# LoRaLo_V30a.net
KiCad netlist of a schematic drawn in EAGLE
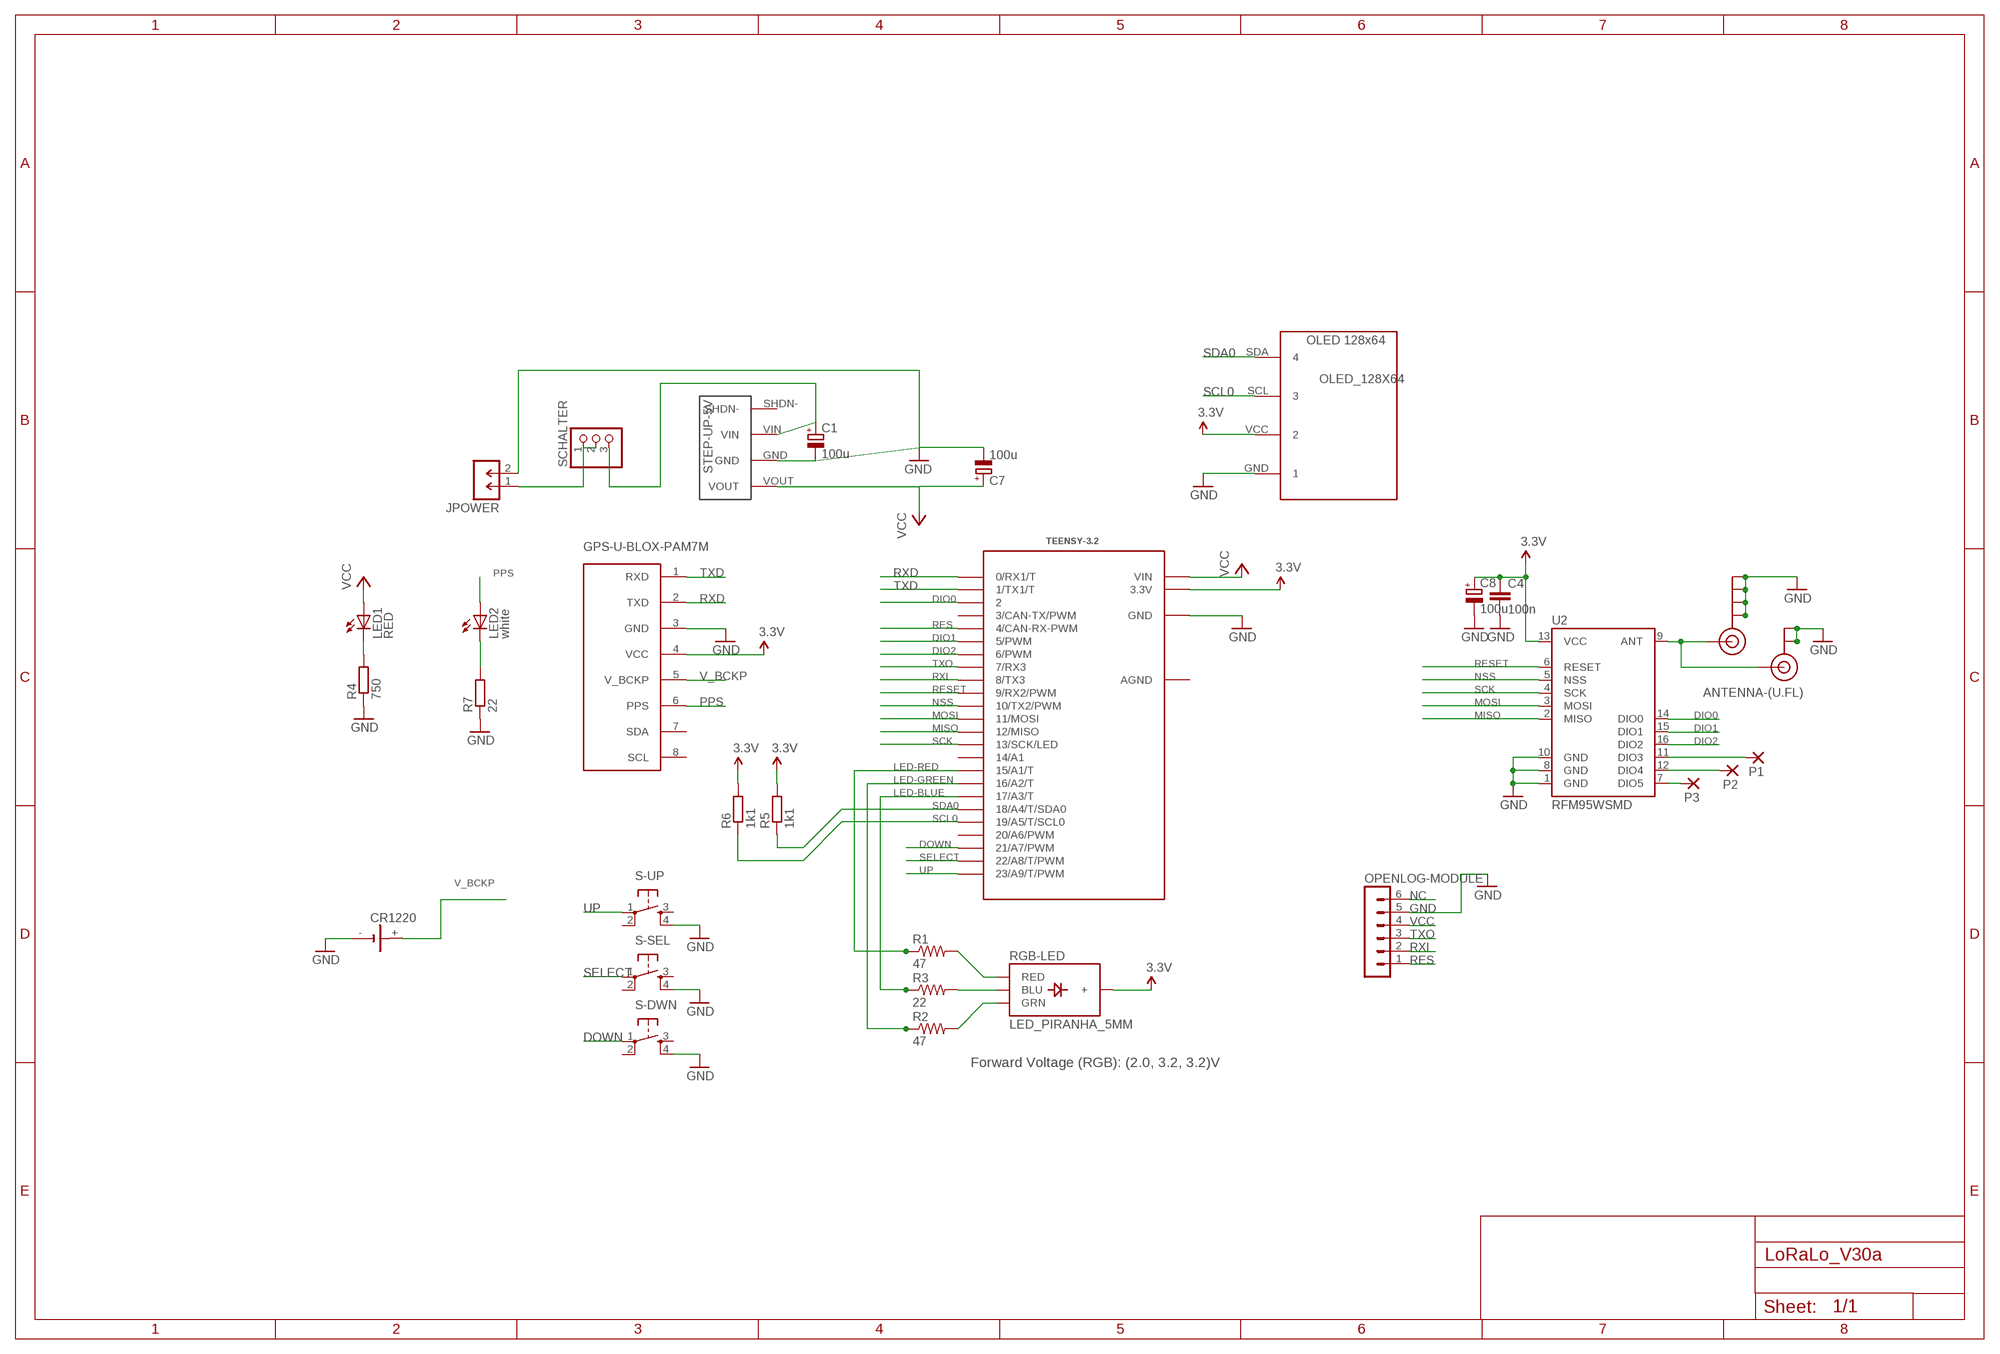
[diagram p0: schematic, sheet 1]

(export (version "E")
  (design (tool "Eeschema 10.0.6"))
  (components
    (comp (ref "ANTENNA-(EDGE-MOUNT)")
      (value "SMA_EDGE")
      (footprint "eagle-import:SMA-EDGE")
      (libsource (lib "eagle-import") (part "SMA_EDGE"))
    )
    (comp (ref "ANTENNA-(U.FL)")
      (value "U.FL")
      (footprint "eagle-import:U.FL")
      (libsource (lib "eagle-import") (part "U.FL"))
    )
    (comp (ref "C1")
      (value "100u")
      (footprint "eagle-import:PANASONIC_D")
      (libsource (lib "eagle-import") (part "CPOL-EUD"))
    )
    (comp (ref "C4")
      (value "100n")
      (footprint "eagle-import:C1206")
      (libsource (lib "eagle-import") (part "C-EUC1206"))
    )
    (comp (ref "C7")
      (value "100u")
      (footprint "eagle-import:PANASONIC_D")
      (libsource (lib "eagle-import") (part "CPOL-EUD"))
    )
    (comp (ref "C8")
      (value "100u")
      (footprint "eagle-import:PANASONIC_D")
      (libsource (lib "eagle-import") (part "CPOL-EUD"))
    )
    (comp (ref "CR1220")
      (value "CH291-1220LF")
      (footprint "eagle-import:CH291-1220LF")
      (libsource (lib "eagle-import") (part "CH291-1220LF"))
    )
    (comp (ref "GPS-U-BLOX-PAM7M")
      (value "U-BLOX-PAM-7Q")
      (footprint "eagle-import:U-BLOX-PAM-7Q")
      (libsource (lib "eagle-import") (part "U-BLOX-PAM-7Q"))
    )
    (comp (ref "JPOWER")
      (value "M-1X02-SIP-100-40")
      (footprint "eagle-import:SIP-100-02-40")
      (libsource (lib "eagle-import") (part "M-1X02-SIP-100-40"))
    )
    (comp (ref "LED1")
      (value "RED")
      (footprint "eagle-import:LED-1206")
      (libsource (lib "eagle-import") (part "LED1206"))
    )
    (comp (ref "LED2")
      (value "white")
      (footprint "eagle-import:LED-1206")
      (libsource (lib "eagle-import") (part "LED1206"))
    )
    (comp (ref "OLED_128X64")
      (value "OLED_128X64")
      (footprint "eagle-import:OLED_128X64")
      (libsource (lib "eagle-import") (part "OLED_128X64"))
    )
    (comp (ref "OPENLOG-MODULE")
      (value "MA06-1")
      (footprint "eagle-import:MA06-1")
      (libsource (lib "eagle-import") (part "MA06-1"))
    )
    (comp (ref "P1")
      (value "1,6/0,8")
      (footprint "eagle-import:1,6_0,8")
      (libsource (lib "eagle-import") (part "1,6/0,8"))
    )
    (comp (ref "P2")
      (value "1,6/0,8")
      (footprint "eagle-import:1,6_0,8")
      (libsource (lib "eagle-import") (part "1,6/0,8"))
    )
    (comp (ref "P3")
      (value "1,6/0,8")
      (footprint "eagle-import:1,6_0,8")
      (libsource (lib "eagle-import") (part "1,6/0,8"))
    )
    (comp (ref "R1")
      (value "47")
      (footprint "eagle-import:1206")
      (libsource (lib "eagle-import") (part "RESISTOR1206"))
    )
    (comp (ref "R2")
      (value "47")
      (footprint "eagle-import:1206")
      (libsource (lib "eagle-import") (part "RESISTOR1206"))
    )
    (comp (ref "R3")
      (value "22")
      (footprint "eagle-import:1206")
      (libsource (lib "eagle-import") (part "RESISTOR1206"))
    )
    (comp (ref "R4")
      (value "750")
      (footprint "eagle-import:M1206")
      (libsource (lib "eagle-import") (part "R-EU_M1206"))
    )
    (comp (ref "R5")
      (value "1k1")
      (footprint "eagle-import:M1206")
      (libsource (lib "eagle-import") (part "R-EU_M1206"))
    )
    (comp (ref "R6")
      (value "1k1")
      (footprint "eagle-import:M1206")
      (libsource (lib "eagle-import") (part "R-EU_M1206"))
    )
    (comp (ref "R7")
      (value "22")
      (footprint "eagle-import:M1206")
      (libsource (lib "eagle-import") (part "R-EU_M1206"))
    )
    (comp (ref "RGB-LED")
      (value "LED_PIRANHA_5MM")
      (footprint "eagle-import:LED_PIRANHA_5MM")
      (libsource (lib "eagle-import") (part "LED_PIRANHA_5MM"))
    )
    (comp (ref "S-DWN")
      (value "TAC_SWITCHPTH")
      (footprint "eagle-import:TACTILE-PTH")
      (libsource (lib "eagle-import") (part "TAC_SWITCHPTH"))
    )
    (comp (ref "S-SEL")
      (value "TAC_SWITCHPTH")
      (footprint "eagle-import:TACTILE-PTH")
      (libsource (lib "eagle-import") (part "TAC_SWITCHPTH"))
    )
    (comp (ref "S-UP")
      (value "TAC_SWITCHPTH")
      (footprint "eagle-import:TACTILE-PTH")
      (libsource (lib "eagle-import") (part "TAC_SWITCHPTH"))
    )
    (comp (ref "SCHALTER")
      (value "PINHD-1X3")
      (footprint "eagle-import:1X03")
      (libsource (lib "eagle-import") (part "PINHD-1X3"))
    )
    (comp (ref "STEP-UP-5V")
      (value "POLOLU_STEP-UP")
      (footprint "eagle-import:POLOLU_STEP-UP")
      (libsource (lib "eagle-import") (part "POLOLU_STEP-UP"))
    )
    (comp (ref "TEENSY-3.2")
      (value "TEENSY_3.1_DIL")
      (footprint "eagle-import:TEENSY3-DIL")
      (libsource (lib "eagle-import") (part "TEENSY_3.1_DIL"))
    )
    (comp (ref "U2")
      (value "RFM95WSMD")
      (footprint "eagle-import:RFM95W_SMD")
      (libsource (lib "eagle-import") (part "RFM95WSMD"))
    )
  )
  (nets
    (net (code "1") (name "/AGND") (class "Default")
      (node (ref "TEENSY-3.2") (pin "AGND") (pinfunction "AGND_AGND") (pintype "power_in"))
    )
    (net (code "2") (name "/DIO0") (class "Default")
      (node (ref "TEENSY-3.2") (pin "2") (pinfunction "2_2") (pintype "bidirectional"))
      (node (ref "U2") (pin "14") (pinfunction "DIO0_14") (pintype "input"))
    )
    (net (code "3") (name "/DIO1") (class "Default")
      (node (ref "TEENSY-3.2") (pin "5") (pinfunction "5/PWM_5") (pintype "bidirectional"))
      (node (ref "U2") (pin "15") (pinfunction "DIO1_15") (pintype "input"))
    )
    (net (code "4") (name "/DIO2") (class "Default")
      (node (ref "TEENSY-3.2") (pin "6") (pinfunction "6/PWM_6") (pintype "bidirectional"))
      (node (ref "U2") (pin "16") (pinfunction "DIO2_16") (pintype "input"))
    )
    (net (code "5") (name "/DOWN") (class "Default")
      (node (ref "S-DWN") (pin "1") (pinfunction "1_1") (pintype "passive"))
      (node (ref "TEENSY-3.2") (pin "21/A7") (pinfunction "21/A7/PWM_21/A7") (pintype "bidirectional"))
    )
    (net (code "6") (name "/LED-BLUE") (class "Default")
      (node (ref "R3") (pin "1") (pinfunction "1_1") (pintype "passive"))
      (node (ref "TEENSY-3.2") (pin "17/A3") (pinfunction "17/A3/T_17/A3") (pintype "bidirectional"))
    )
    (net (code "7") (name "/LED-GREEN") (class "Default")
      (node (ref "R2") (pin "1") (pinfunction "1_1") (pintype "passive"))
      (node (ref "TEENSY-3.2") (pin "16/A2") (pinfunction "16/A2/T_16/A2") (pintype "bidirectional"))
    )
    (net (code "8") (name "/LED-RED") (class "Default")
      (node (ref "R1") (pin "1") (pinfunction "1_1") (pintype "passive"))
      (node (ref "TEENSY-3.2") (pin "15/A1") (pinfunction "15/A1/T_15/A1") (pintype "bidirectional"))
    )
    (net (code "9") (name "/MISO") (class "Default")
      (node (ref "TEENSY-3.2") (pin "12") (pinfunction "12/MISO_12") (pintype "bidirectional"))
      (node (ref "U2") (pin "2") (pinfunction "MISO_2") (pintype "output"))
    )
    (net (code "10") (name "/MOSI") (class "Default")
      (node (ref "TEENSY-3.2") (pin "11") (pinfunction "11/MOSI_11") (pintype "bidirectional"))
      (node (ref "U2") (pin "3") (pinfunction "MOSI_3") (pintype "input"))
    )
    (net (code "11") (name "/NC") (class "Default")
      (node (ref "OPENLOG-MODULE") (pin "6") (pinfunction "6_6") (pintype "passive"))
    )
    (net (code "12") (name "/NSS") (class "Default")
      (node (ref "TEENSY-3.2") (pin "10") (pinfunction "10/TX2/PWM_10") (pintype "bidirectional"))
      (node (ref "U2") (pin "5") (pinfunction "NSS_5") (pintype "input"))
    )
    (net (code "13") (name "/PPS") (class "Default")
      (node (ref "GPS-U-BLOX-PAM7M") (pin "6") (pinfunction "PPS_6") (pintype "bidirectional"))
      (node (ref "LED2") (pin "A") (pinfunction "A_A") (pintype "passive"))
    )
    (net (code "14") (name "/RES") (class "Default")
      (node (ref "OPENLOG-MODULE") (pin "1") (pinfunction "1_1") (pintype "passive"))
      (node (ref "TEENSY-3.2") (pin "4") (pinfunction "4/CAN-RX-PWM_4") (pintype "bidirectional"))
    )
    (net (code "15") (name "/RESET") (class "Default")
      (node (ref "TEENSY-3.2") (pin "9") (pinfunction "9/RX2/PWM_9") (pintype "bidirectional"))
      (node (ref "U2") (pin "6") (pinfunction "RESET_6") (pintype "output"))
    )
    (net (code "16") (name "/RXD") (class "Default")
      (node (ref "GPS-U-BLOX-PAM7M") (pin "2") (pinfunction "TXD_2") (pintype "bidirectional"))
      (node (ref "TEENSY-3.2") (pin "0") (pinfunction "0/RX1/T_0") (pintype "bidirectional"))
    )
    (net (code "17") (name "/RXI") (class "Default")
      (node (ref "OPENLOG-MODULE") (pin "2") (pinfunction "2_2") (pintype "passive"))
      (node (ref "TEENSY-3.2") (pin "8") (pinfunction "8/TX3_8") (pintype "bidirectional"))
    )
    (net (code "18") (name "/SCK") (class "Default")
      (node (ref "TEENSY-3.2") (pin "13") (pinfunction "13/SCK/LED_13") (pintype "bidirectional"))
      (node (ref "U2") (pin "4") (pinfunction "SCK_4") (pintype "input"))
    )
    (net (code "19") (name "/SCL0") (class "Default")
      (node (ref "OLED_128X64") (pin "SCL") (pinfunction "3_SCL") (pintype "bidirectional"))
      (node (ref "R6") (pin "1") (pinfunction "1_1") (pintype "passive"))
      (node (ref "TEENSY-3.2") (pin "19/A5") (pinfunction "19/A5/T/SCL0_19/A5") (pintype "bidirectional"))
    )
    (net (code "20") (name "/SDA0") (class "Default")
      (node (ref "OLED_128X64") (pin "SDA") (pinfunction "4_SDA") (pintype "bidirectional"))
      (node (ref "R5") (pin "1") (pinfunction "1_1") (pintype "passive"))
      (node (ref "TEENSY-3.2") (pin "18/A4") (pinfunction "18/A4/T/SDA0_18/A4") (pintype "bidirectional"))
    )
    (net (code "21") (name "/SELECT") (class "Default")
      (node (ref "S-SEL") (pin "1") (pinfunction "1_1") (pintype "passive"))
      (node (ref "TEENSY-3.2") (pin "22/A8") (pinfunction "22/A8/T/PWM_22/A8") (pintype "bidirectional"))
    )
    (net (code "22") (name "/TXD") (class "Default")
      (node (ref "GPS-U-BLOX-PAM7M") (pin "1") (pinfunction "RXD_1") (pintype "bidirectional"))
      (node (ref "TEENSY-3.2") (pin "1") (pinfunction "1/TX1/T_1") (pintype "bidirectional"))
    )
    (net (code "23") (name "/TXO") (class "Default")
      (node (ref "OPENLOG-MODULE") (pin "3") (pinfunction "3_3") (pintype "passive"))
      (node (ref "TEENSY-3.2") (pin "7") (pinfunction "7/RX3_7") (pintype "bidirectional"))
    )
    (net (code "24") (name "/UP") (class "Default")
      (node (ref "S-UP") (pin "1") (pinfunction "1_1") (pintype "passive"))
      (node (ref "TEENSY-3.2") (pin "23/A9") (pinfunction "23/A9/T/PWM_23/A9") (pintype "bidirectional"))
    )
    (net (code "25") (name "/V_BCKP") (class "Default")
      (node (ref "CR1220") (pin "+") (pinfunction "+_+") (pintype "passive"))
      (node (ref "GPS-U-BLOX-PAM7M") (pin "5") (pinfunction "V_BCKP_5") (pintype "bidirectional"))
    )
    (net (code "26") (name "3.3V") (class "Default")
      (node (ref "C4") (pin "1") (pinfunction "1_1") (pintype "passive"))
      (node (ref "C8") (pin "+") (pinfunction "+_+") (pintype "passive"))
      (node (ref "GPS-U-BLOX-PAM7M") (pin "4") (pinfunction "VCC_4") (pintype "bidirectional"))
      (node (ref "OLED_128X64") (pin "VCC") (pinfunction "2_VCC") (pintype "bidirectional"))
      (node (ref "R5") (pin "2") (pinfunction "2_2") (pintype "passive"))
      (node (ref "R6") (pin "2") (pinfunction "2_2") (pintype "passive"))
      (node (ref "RGB-LED") (pin "+") (pinfunction "+_+") (pintype "bidirectional"))
      (node (ref "TEENSY-3.2") (pin "3.3V") (pinfunction "3.3V_3.3V") (pintype "power_in"))
      (node (ref "U2") (pin "13") (pinfunction "VCC_13") (pintype "bidirectional"))
    )
    (net (code "27") (name "GND") (class "Default")
      (node (ref "ANTENNA-(EDGE-MOUNT)") (pin "GND@0") (pinfunction "GND_GND@0") (pintype "bidirectional"))
      (node (ref "ANTENNA-(EDGE-MOUNT)") (pin "GND@1") (pinfunction "GND_GND@1") (pintype "bidirectional"))
      (node (ref "ANTENNA-(EDGE-MOUNT)") (pin "GND@2") (pinfunction "GND_GND@2") (pintype "bidirectional"))
      (node (ref "ANTENNA-(EDGE-MOUNT)") (pin "GND@3") (pinfunction "GND_GND@3") (pintype "bidirectional"))
      (node (ref "ANTENNA-(U.FL)") (pin "P$1") (pinfunction "GND_P$1") (pintype "bidirectional"))
      (node (ref "ANTENNA-(U.FL)") (pin "P$2") (pinfunction "GND_P$2") (pintype "bidirectional"))
      (node (ref "C1") (pin "-") (pinfunction "-_-") (pintype "passive"))
      (node (ref "C4") (pin "2") (pinfunction "2_2") (pintype "passive"))
      (node (ref "C7") (pin "-") (pinfunction "-_-") (pintype "passive"))
      (node (ref "C8") (pin "-") (pinfunction "-_-") (pintype "passive"))
      (node (ref "CR1220") (pin "-") (pinfunction "-_-") (pintype "passive"))
      (node (ref "GPS-U-BLOX-PAM7M") (pin "3") (pinfunction "GND_3") (pintype "bidirectional"))
      (node (ref "JPOWER") (pin "2") (pinfunction "2_2") (pintype "passive"))
      (node (ref "OLED_128X64") (pin "GND") (pinfunction "1_GND") (pintype "bidirectional"))
      (node (ref "OPENLOG-MODULE") (pin "5") (pinfunction "5_5") (pintype "passive"))
      (node (ref "R4") (pin "1") (pinfunction "1_1") (pintype "passive"))
      (node (ref "R7") (pin "1") (pinfunction "1_1") (pintype "passive"))
      (node (ref "S-DWN") (pin "4") (pinfunction "4_4") (pintype "passive"))
      (node (ref "S-SEL") (pin "4") (pinfunction "4_4") (pintype "passive"))
      (node (ref "S-UP") (pin "4") (pinfunction "4_4") (pintype "passive"))
      (node (ref "STEP-UP-5V") (pin "GND") (pinfunction "GND_GND") (pintype "bidirectional"))
      (node (ref "TEENSY-3.2") (pin "GND") (pinfunction "GND_GND") (pintype "power_in"))
      (node (ref "U2") (pin "1") (pinfunction "GND_1") (pintype "power_in"))
      (node (ref "U2") (pin "10") (pinfunction "GND_10") (pintype "power_in"))
      (node (ref "U2") (pin "8") (pinfunction "GND_8") (pintype "power_in"))
    )
    (net (code "28") (name "Net-(ANTENNA-(EDGE-MOUNT)-SIGNAL)") (class "Default")
      (node (ref "ANTENNA-(EDGE-MOUNT)") (pin "SIG") (pinfunction "SIGNAL_SIG") (pintype "bidirectional"))
      (node (ref "ANTENNA-(U.FL)") (pin "P$3") (pinfunction "SIGNAL_P$3") (pintype "bidirectional"))
      (node (ref "U2") (pin "9") (pinfunction "ANT_9") (pintype "bidirectional"))
    )
    (net (code "29") (name "Net-(C1-Pad+)") (class "Default")
      (node (ref "C1") (pin "+") (pinfunction "+_+") (pintype "passive"))
      (node (ref "SCHALTER") (pin "3") (pinfunction "3_3") (pintype "passive"))
      (node (ref "STEP-UP-5V") (pin "VIN") (pinfunction "VIN_VIN") (pintype "bidirectional"))
    )
    (net (code "30") (name "Net-(JPOWER-Pad1)") (class "Default")
      (node (ref "JPOWER") (pin "1") (pinfunction "1_1") (pintype "passive"))
      (node (ref "SCHALTER") (pin "1") (pinfunction "1_1") (pintype "passive"))
      (node (ref "SCHALTER") (pin "2") (pinfunction "2_2") (pintype "passive"))
    )
    (net (code "31") (name "Net-(LED1-PadC)") (class "Default")
      (node (ref "LED1") (pin "C") (pinfunction "C_C") (pintype "passive"))
      (node (ref "R4") (pin "2") (pinfunction "2_2") (pintype "passive"))
    )
    (net (code "32") (name "Net-(LED2-PadC)") (class "Default")
      (node (ref "LED2") (pin "C") (pinfunction "C_C") (pintype "passive"))
      (node (ref "R7") (pin "2") (pinfunction "2_2") (pintype "passive"))
    )
    (net (code "33") (name "Net-(P1-P)") (class "Default")
      (node (ref "P1") (pin "1") (pinfunction "P_1") (pintype "passive"))
      (node (ref "U2") (pin "11") (pinfunction "DIO3_11") (pintype "bidirectional"))
    )
    (net (code "34") (name "Net-(P2-P)") (class "Default")
      (node (ref "P2") (pin "1") (pinfunction "P_1") (pintype "passive"))
      (node (ref "U2") (pin "12") (pinfunction "DIO4_12") (pintype "bidirectional"))
    )
    (net (code "35") (name "Net-(P3-P)") (class "Default")
      (node (ref "P3") (pin "1") (pinfunction "P_1") (pintype "passive"))
      (node (ref "U2") (pin "7") (pinfunction "DIO5_7") (pintype "bidirectional"))
    )
    (net (code "36") (name "Net-(RGB-LED-BLU)") (class "Default")
      (node (ref "R3") (pin "2") (pinfunction "2_2") (pintype "passive"))
      (node (ref "RGB-LED") (pin "B") (pinfunction "BLU_B") (pintype "bidirectional"))
    )
    (net (code "37") (name "Net-(RGB-LED-GRN)") (class "Default")
      (node (ref "R2") (pin "2") (pinfunction "2_2") (pintype "passive"))
      (node (ref "RGB-LED") (pin "G") (pinfunction "GRN_G") (pintype "bidirectional"))
    )
    (net (code "38") (name "Net-(RGB-LED-RED)") (class "Default")
      (node (ref "R1") (pin "2") (pinfunction "2_2") (pintype "passive"))
      (node (ref "RGB-LED") (pin "R") (pinfunction "RED_R") (pintype "bidirectional"))
    )
    (net (code "39") (name "VCC") (class "Default")
      (node (ref "C7") (pin "+") (pinfunction "+_+") (pintype "passive"))
      (node (ref "LED1") (pin "A") (pinfunction "A_A") (pintype "passive"))
      (node (ref "OPENLOG-MODULE") (pin "4") (pinfunction "4_4") (pintype "passive"))
      (node (ref "STEP-UP-5V") (pin "VOUT") (pinfunction "VOUT_VOUT") (pintype "bidirectional"))
      (node (ref "TEENSY-3.2") (pin "VIN") (pinfunction "VIN_VIN") (pintype "power_in"))
    )
    (net (code "40") (name "unconnected-(GPS-U-BLOX-PAM7M-SCL-Pad8)") (class "Default")
      (node (ref "GPS-U-BLOX-PAM7M") (pin "8") (pinfunction "SCL_8") (pintype "bidirectional"))
    )
    (net (code "41") (name "unconnected-(GPS-U-BLOX-PAM7M-SDA-Pad7)") (class "Default")
      (node (ref "GPS-U-BLOX-PAM7M") (pin "7") (pinfunction "SDA_7") (pintype "bidirectional"))
    )
    (net (code "42") (name "unconnected-(S-DWN-Pad2)") (class "Default")
      (node (ref "S-DWN") (pin "2") (pinfunction "2_2") (pintype "passive"))
    )
    (net (code "43") (name "unconnected-(S-DWN-Pad3)") (class "Default")
      (node (ref "S-DWN") (pin "3") (pinfunction "3_3") (pintype "passive"))
    )
    (net (code "44") (name "unconnected-(S-SEL-Pad2)") (class "Default")
      (node (ref "S-SEL") (pin "2") (pinfunction "2_2") (pintype "passive"))
    )
    (net (code "45") (name "unconnected-(S-SEL-Pad3)") (class "Default")
      (node (ref "S-SEL") (pin "3") (pinfunction "3_3") (pintype "passive"))
    )
    (net (code "46") (name "unconnected-(S-UP-Pad2)") (class "Default")
      (node (ref "S-UP") (pin "2") (pinfunction "2_2") (pintype "passive"))
    )
    (net (code "47") (name "unconnected-(S-UP-Pad3)") (class "Default")
      (node (ref "S-UP") (pin "3") (pinfunction "3_3") (pintype "passive"))
    )
    (net (code "48") (name "unconnected-(STEP-UP-5V-PadSHDN-)") (class "Default")
      (node (ref "STEP-UP-5V") (pin "SHDN-") (pinfunction "SHDN-_SHDN-") (pintype "bidirectional"))
    )
    (net (code "49") (name "unconnected-(TEENSY-3.2-3{slash}CAN-TX{slash}PWM-Pad3)") (class "Default")
      (node (ref "TEENSY-3.2") (pin "3") (pinfunction "3/CAN-TX/PWM_3") (pintype "bidirectional"))
    )
    (net (code "50") (name "unconnected-(TEENSY-3.2-14{slash}A1-Pad14{slash}A0)") (class "Default")
      (node (ref "TEENSY-3.2") (pin "14/A0") (pinfunction "14/A1_14/A0") (pintype "bidirectional"))
    )
    (net (code "51") (name "unconnected-(TEENSY-3.2-20{slash}A6{slash}PWM-Pad20{slash}A6)") (class "Default")
      (node (ref "TEENSY-3.2") (pin "20/A6") (pinfunction "20/A6/PWM_20/A6") (pintype "bidirectional"))
    )
  )
)
